# SilentStepStick-TMC2208_v11.net
KiCad netlist of a schematic drawn in EAGLE
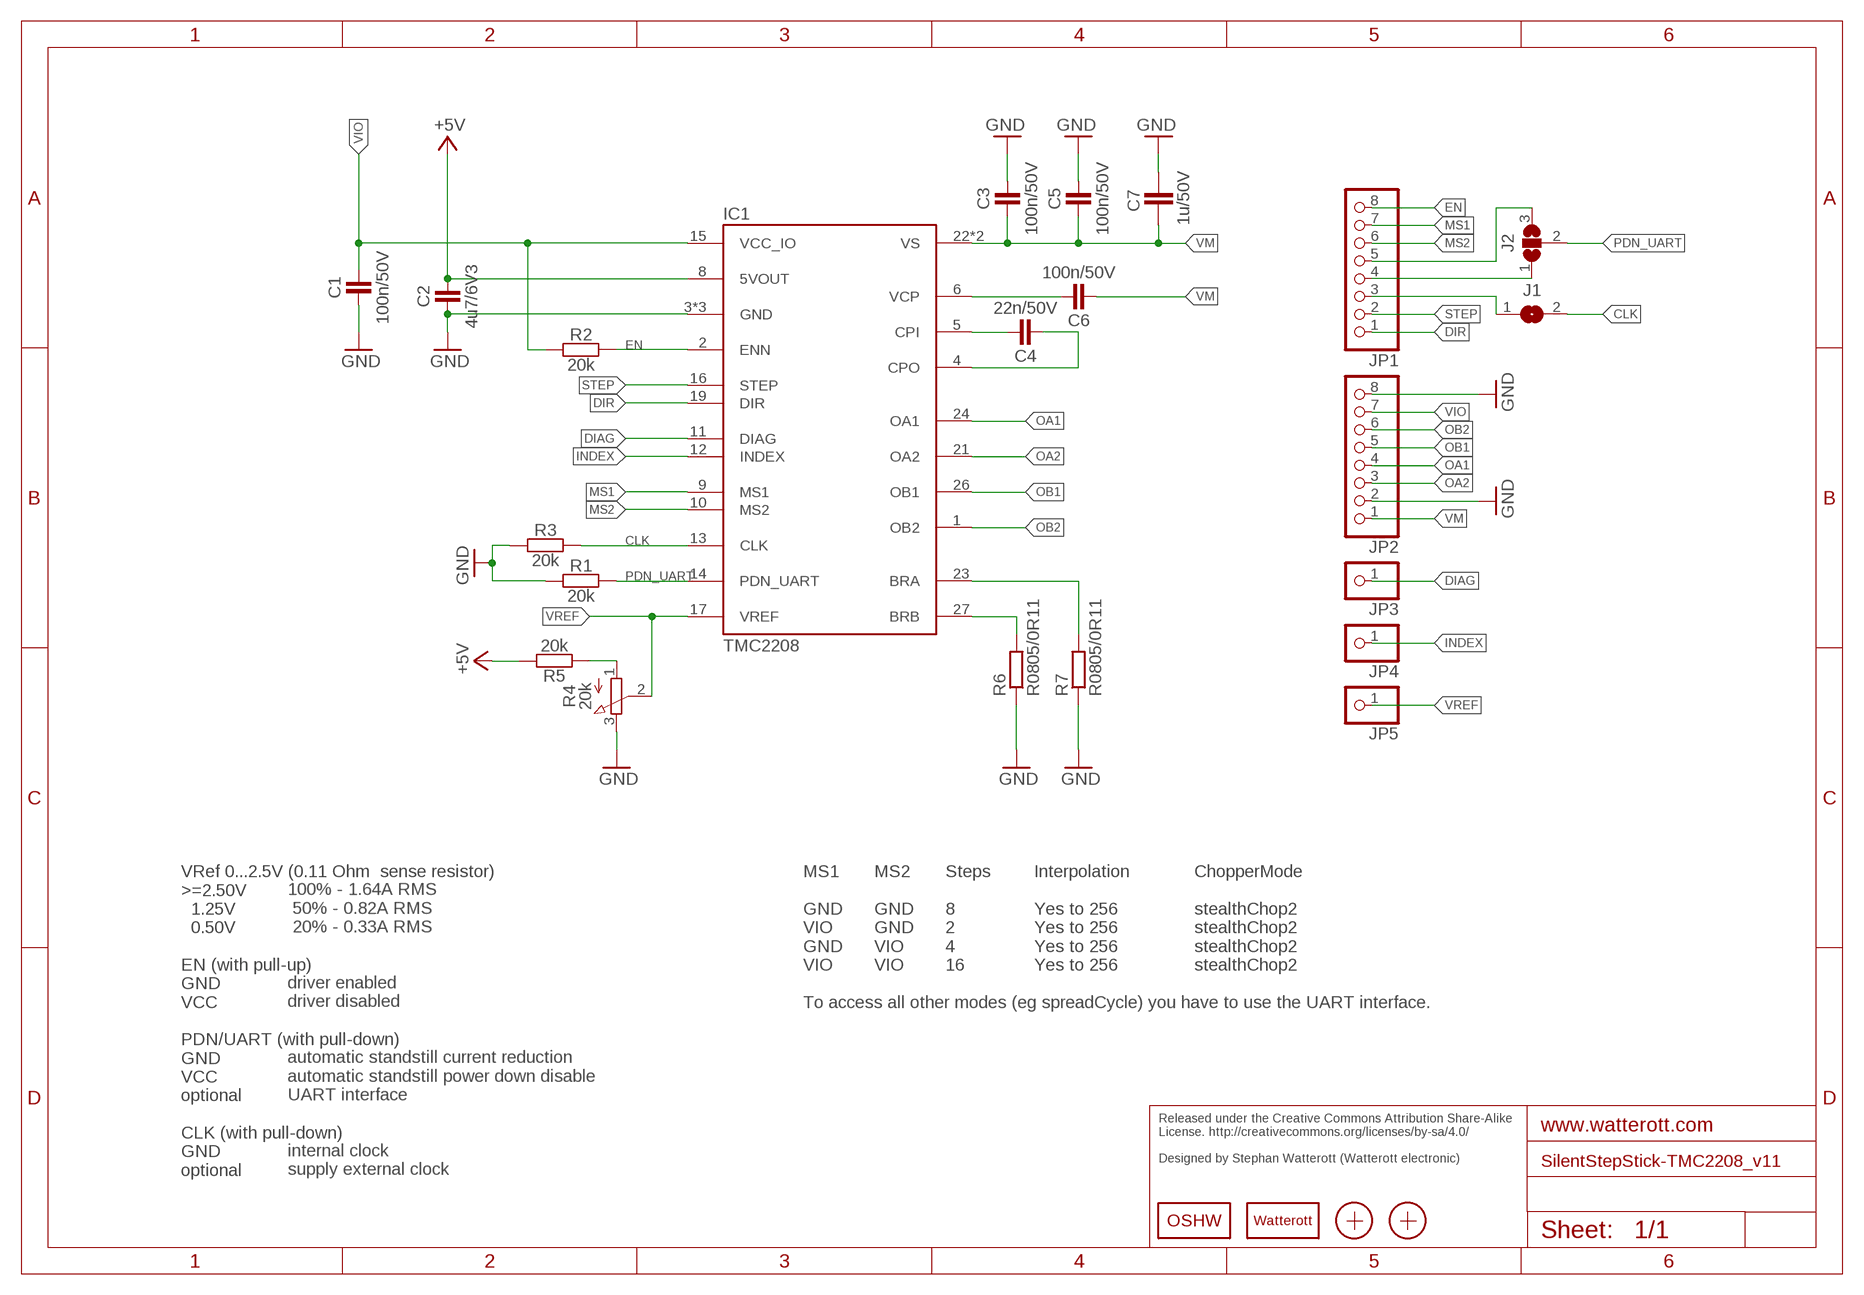
[diagram p0: schematic, sheet 1]

(export (version "E")
  (design (tool "Eeschema 10.0.6"))
  (components
    (comp (ref "C1")
      (value "100n/50V")
      (footprint "eagle-import:C0402")
      (libsource (lib "eagle-import") (part "CAPACITOR-0402"))
    )
    (comp (ref "C2")
      (value "4u7/6V3")
      (footprint "eagle-import:C0402")
      (libsource (lib "eagle-import") (part "CAPACITOR-0402"))
    )
    (comp (ref "C3")
      (value "100n/50V")
      (footprint "eagle-import:C0402")
      (libsource (lib "eagle-import") (part "CAPACITOR-0402"))
    )
    (comp (ref "C4")
      (value "22n/50V")
      (footprint "eagle-import:C0402")
      (libsource (lib "eagle-import") (part "CAPACITOR-0402"))
    )
    (comp (ref "C5")
      (value "100n/50V")
      (footprint "eagle-import:C0402")
      (libsource (lib "eagle-import") (part "CAPACITOR-0402"))
    )
    (comp (ref "C6")
      (value "100n/50V")
      (footprint "eagle-import:C0402")
      (libsource (lib "eagle-import") (part "CAPACITOR-0402"))
    )
    (comp (ref "C7")
      (value "1u/50V")
      (footprint "eagle-import:C0805")
      (libsource (lib "eagle-import") (part "C-EUC0805"))
    )
    (comp (ref "IC1")
      (value "TMC2208")
      (footprint "eagle-import:QFN28-PAD")
      (libsource (lib "eagle-import") (part "TMC2208"))
    )
    (comp (ref "J1")
      (value "JUMPER2-0402")
      (footprint "eagle-import:JUMPER2-0402")
      (libsource (lib "eagle-import") (part "JUMPER2-0402"))
    )
    (comp (ref "J2")
      (value "JUMPER3-0402-NC")
      (footprint "eagle-import:JUMPER3-0402_NC")
      (libsource (lib "eagle-import") (part "JUMPER3-0402-NC"))
    )
    (comp (ref "JP1")
      (value "PINHD-1X08_2.54-S")
      (footprint "eagle-import:1X08-S")
      (libsource (lib "eagle-import") (part "PINHD-1X08_2.54-S"))
    )
    (comp (ref "JP2")
      (value "PINHD-1X08_2.54-S")
      (footprint "eagle-import:1X08-S")
      (libsource (lib "eagle-import") (part "PINHD-1X08_2.54-S"))
    )
    (comp (ref "JP3")
      (value "PINHD-1X1")
      (footprint "eagle-import:1X01")
      (libsource (lib "eagle-import") (part "PINHD-1X1"))
    )
    (comp (ref "JP4")
      (value "PINHD-1X1")
      (footprint "eagle-import:1X01")
      (libsource (lib "eagle-import") (part "PINHD-1X1"))
    )
    (comp (ref "JP5")
      (value "PINHD-1X1")
      (footprint "eagle-import:1X01")
      (libsource (lib "eagle-import") (part "PINHD-1X1"))
    )
    (comp (ref "LOGO1")
      (value "OSHW_LOGOX0070")
      (footprint "eagle-import:OSHW_6X70")
      (libsource (lib "eagle-import") (part "OSHW_LOGOX0070"))
    )
    (comp (ref "LOGO2")
      (value "LOGO-S_PLACE_M")
      (footprint "eagle-import:SPARK_TPLACE_M")
      (libsource (lib "eagle-import") (part "LOGO-S_PLACE_M"))
    )
    (comp (ref "R1")
      (value "20k")
      (footprint "eagle-import:C0402")
      (libsource (lib "eagle-import") (part "RESISTOR-0402"))
    )
    (comp (ref "R2")
      (value "20k")
      (footprint "eagle-import:C0402")
      (libsource (lib "eagle-import") (part "RESISTOR-0402"))
    )
    (comp (ref "R3")
      (value "20k")
      (footprint "eagle-import:C0402")
      (libsource (lib "eagle-import") (part "RESISTOR-0402"))
    )
    (comp (ref "R4")
      (value "20k")
      (footprint "eagle-import:POT_EVM3R")
      (libsource (lib "eagle-import") (part "POTEVM3R"))
    )
    (comp (ref "R5")
      (value "20k")
      (footprint "eagle-import:C0402")
      (libsource (lib "eagle-import") (part "RESISTOR-0402"))
    )
    (comp (ref "R6")
      (value "R0805/0R11")
      (footprint "eagle-import:M0805")
      (libsource (lib "eagle-import") (part "R-EU_M0805"))
    )
    (comp (ref "R7")
      (value "R0805/0R11")
      (footprint "eagle-import:M0805")
      (libsource (lib "eagle-import") (part "R-EU_M0805"))
    )
    (comp (ref "X1")
      (value "PASSER-04")
      (footprint "eagle-import:PASSER_04MM")
      (libsource (lib "eagle-import") (part "PASSER-04"))
    )
    (comp (ref "X2")
      (value "PASSER-04")
      (footprint "eagle-import:PASSER_04MM")
      (libsource (lib "eagle-import") (part "PASSER-04"))
    )
  )
  (nets
    (net (code "1") (name "+5V") (class "Default")
      (node (ref "C2") (pin "2") (pinfunction "2_2") (pintype "passive"))
      (node (ref "IC1") (pin "8") (pinfunction "5VOUT_8") (pintype "power_in"))
      (node (ref "R5") (pin "2") (pinfunction "2_2") (pintype "passive"))
    )
    (net (code "2") (name "CLK") (class "Default")
      (node (ref "IC1") (pin "13") (pinfunction "CLK_13") (pintype "bidirectional"))
      (node (ref "J1") (pin "2") (pinfunction "2_2") (pintype "passive"))
      (node (ref "R3") (pin "2") (pinfunction "2_2") (pintype "passive"))
    )
    (net (code "3") (name "DIAG") (class "Default")
      (node (ref "IC1") (pin "11") (pinfunction "DIAG_11") (pintype "bidirectional"))
      (node (ref "JP3") (pin "1") (pinfunction "1_1") (pintype "passive"))
    )
    (net (code "4") (name "DIR") (class "Default")
      (node (ref "IC1") (pin "19") (pinfunction "DIR_19") (pintype "bidirectional"))
      (node (ref "JP1") (pin "1") (pinfunction "1_1") (pintype "passive"))
    )
    (net (code "5") (name "EN") (class "Default")
      (node (ref "IC1") (pin "2") (pinfunction "ENN_2") (pintype "bidirectional"))
      (node (ref "JP1") (pin "8") (pinfunction "8_8") (pintype "passive"))
      (node (ref "R2") (pin "2") (pinfunction "2_2") (pintype "passive"))
    )
    (net (code "6") (name "GND") (class "Default")
      (node (ref "C1") (pin "1") (pinfunction "1_1") (pintype "passive"))
      (node (ref "C2") (pin "1") (pinfunction "1_1") (pintype "passive"))
      (node (ref "C3") (pin "2") (pinfunction "2_2") (pintype "passive"))
      (node (ref "C5") (pin "2") (pinfunction "2_2") (pintype "passive"))
      (node (ref "C7") (pin "2") (pinfunction "2_2") (pintype "passive"))
      (node (ref "IC1") (pin "18") (pinfunction "GND_18") (pintype "power_in"))
      (node (ref "IC1") (pin "3") (pinfunction "GND_3") (pintype "power_in"))
      (node (ref "IC1") (pin "TP") (pinfunction "GND_TP") (pintype "power_in"))
      (node (ref "JP2") (pin "2") (pinfunction "2_2") (pintype "passive"))
      (node (ref "JP2") (pin "8") (pinfunction "8_8") (pintype "passive"))
      (node (ref "R1") (pin "1") (pinfunction "1_1") (pintype "passive"))
      (node (ref "R3") (pin "1") (pinfunction "1_1") (pintype "passive"))
      (node (ref "R4") (pin "3") (pinfunction "E_3") (pintype "passive"))
      (node (ref "R6") (pin "1") (pinfunction "1_1") (pintype "passive"))
      (node (ref "R7") (pin "1") (pinfunction "1_1") (pintype "passive"))
    )
    (net (code "7") (name "INDEX") (class "Default")
      (node (ref "IC1") (pin "12") (pinfunction "INDEX_12") (pintype "bidirectional"))
      (node (ref "JP4") (pin "1") (pinfunction "1_1") (pintype "passive"))
    )
    (net (code "8") (name "MS1") (class "Default")
      (node (ref "IC1") (pin "9") (pinfunction "MS1_9") (pintype "bidirectional"))
      (node (ref "JP1") (pin "7") (pinfunction "7_7") (pintype "passive"))
    )
    (net (code "9") (name "MS2") (class "Default")
      (node (ref "IC1") (pin "10") (pinfunction "MS2_10") (pintype "bidirectional"))
      (node (ref "JP1") (pin "6") (pinfunction "6_6") (pintype "passive"))
    )
    (net (code "10") (name "Net-(IC1-BRA)") (class "Default")
      (node (ref "IC1") (pin "23") (pinfunction "BRA_23") (pintype "output"))
      (node (ref "R7") (pin "2") (pinfunction "2_2") (pintype "passive"))
    )
    (net (code "11") (name "Net-(IC1-BRB)") (class "Default")
      (node (ref "IC1") (pin "27") (pinfunction "BRB_27") (pintype "output"))
      (node (ref "R6") (pin "2") (pinfunction "2_2") (pintype "passive"))
    )
    (net (code "12") (name "Net-(IC1-CPI)") (class "Default")
      (node (ref "C4") (pin "2") (pinfunction "2_2") (pintype "passive"))
      (node (ref "IC1") (pin "5") (pinfunction "CPI_5") (pintype "passive"))
    )
    (net (code "13") (name "Net-(IC1-CPO)") (class "Default")
      (node (ref "C4") (pin "1") (pinfunction "1_1") (pintype "passive"))
      (node (ref "IC1") (pin "4") (pinfunction "CPO_4") (pintype "passive"))
    )
    (net (code "14") (name "Net-(IC1-VCP)") (class "Default")
      (node (ref "C6") (pin "2") (pinfunction "2_2") (pintype "passive"))
      (node (ref "IC1") (pin "6") (pinfunction "VCP_6") (pintype "passive"))
    )
    (net (code "15") (name "Net-(J1-Pad1)") (class "Default")
      (node (ref "J1") (pin "1") (pinfunction "1_1") (pintype "passive"))
      (node (ref "JP1") (pin "3") (pinfunction "3_3") (pintype "passive"))
    )
    (net (code "16") (name "Net-(J2-Pad1)") (class "Default")
      (node (ref "J2") (pin "1") (pinfunction "1_1") (pintype "passive"))
      (node (ref "JP1") (pin "4") (pinfunction "4_4") (pintype "passive"))
    )
    (net (code "17") (name "Net-(J2-Pad3)") (class "Default")
      (node (ref "J2") (pin "3") (pinfunction "3_3") (pintype "passive"))
      (node (ref "JP1") (pin "5") (pinfunction "5_5") (pintype "passive"))
    )
    (net (code "18") (name "Net-(R4-A)") (class "Default")
      (node (ref "R4") (pin "1") (pinfunction "A_1") (pintype "passive"))
      (node (ref "R5") (pin "1") (pinfunction "1_1") (pintype "passive"))
    )
    (net (code "19") (name "OA1") (class "Default")
      (node (ref "IC1") (pin "24") (pinfunction "OA1_24") (pintype "output"))
      (node (ref "JP2") (pin "4") (pinfunction "4_4") (pintype "passive"))
    )
    (net (code "20") (name "OA2") (class "Default")
      (node (ref "IC1") (pin "21") (pinfunction "OA2_21") (pintype "output"))
      (node (ref "JP2") (pin "3") (pinfunction "3_3") (pintype "passive"))
    )
    (net (code "21") (name "OB1") (class "Default")
      (node (ref "IC1") (pin "26") (pinfunction "OB1_26") (pintype "output"))
      (node (ref "JP2") (pin "5") (pinfunction "5_5") (pintype "passive"))
    )
    (net (code "22") (name "OB2") (class "Default")
      (node (ref "IC1") (pin "1") (pinfunction "OB2_1") (pintype "output"))
      (node (ref "JP2") (pin "6") (pinfunction "6_6") (pintype "passive"))
    )
    (net (code "23") (name "PDN_UART") (class "Default")
      (node (ref "IC1") (pin "14") (pinfunction "PDN_UART_14") (pintype "bidirectional"))
      (node (ref "J2") (pin "2") (pinfunction "2_2") (pintype "passive"))
      (node (ref "R1") (pin "2") (pinfunction "2_2") (pintype "passive"))
    )
    (net (code "24") (name "STEP") (class "Default")
      (node (ref "IC1") (pin "16") (pinfunction "STEP_16") (pintype "bidirectional"))
      (node (ref "JP1") (pin "2") (pinfunction "2_2") (pintype "passive"))
    )
    (net (code "25") (name "VIO") (class "Default")
      (node (ref "C1") (pin "2") (pinfunction "2_2") (pintype "passive"))
      (node (ref "IC1") (pin "15") (pinfunction "VCC_IO_15") (pintype "power_in"))
      (node (ref "JP2") (pin "7") (pinfunction "7_7") (pintype "passive"))
      (node (ref "R2") (pin "1") (pinfunction "1_1") (pintype "passive"))
    )
    (net (code "26") (name "VM") (class "Default")
      (node (ref "C3") (pin "1") (pinfunction "1_1") (pintype "passive"))
      (node (ref "C5") (pin "1") (pinfunction "1_1") (pintype "passive"))
      (node (ref "C6") (pin "1") (pinfunction "1_1") (pintype "passive"))
      (node (ref "C7") (pin "1") (pinfunction "1_1") (pintype "passive"))
      (node (ref "IC1") (pin "22") (pinfunction "VS_22") (pintype "power_in"))
      (node (ref "IC1") (pin "28") (pinfunction "VS_28") (pintype "power_in"))
      (node (ref "JP2") (pin "1") (pinfunction "1_1") (pintype "passive"))
    )
    (net (code "27") (name "VREF") (class "Default")
      (node (ref "IC1") (pin "17") (pinfunction "VREF_17") (pintype "passive"))
      (node (ref "JP5") (pin "1") (pinfunction "1_1") (pintype "passive"))
      (node (ref "R4") (pin "2") (pinfunction "S_2") (pintype "passive"))
    )
  )
)
